# M119B.net
KiCad netlist of a schematic drawn in EAGLE
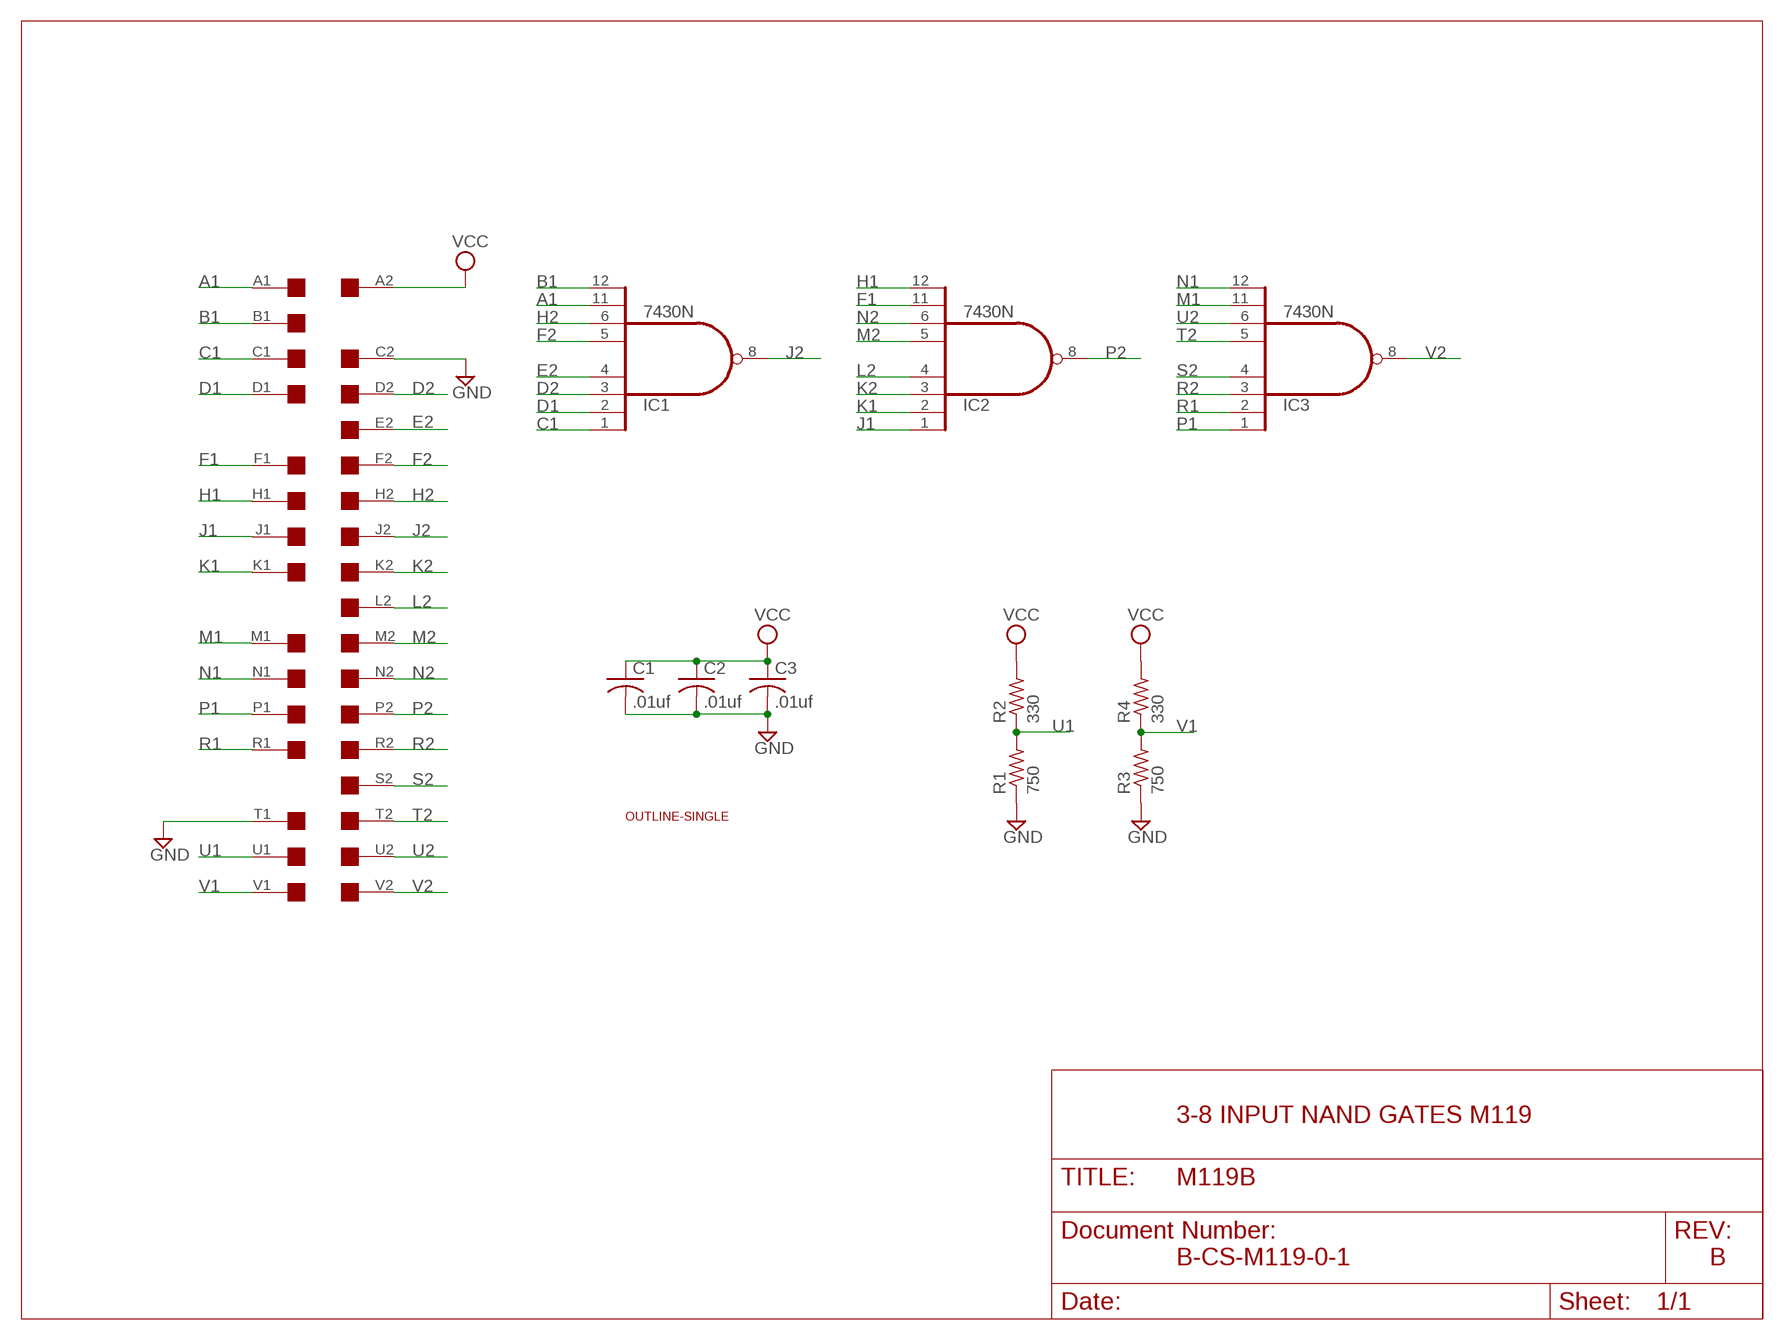
[diagram p0: schematic, sheet 1]

(export (version "E")
  (design (tool "Eeschema 10.0.6"))
  (components
    (comp (ref "C1")
      (value ".01uf")
      (footprint "eagle-import:C050-025X075")
      (libsource (lib "eagle-import") (part "C-US050-025X075"))
    )
    (comp (ref "C2")
      (value ".01uf")
      (footprint "eagle-import:C050-025X075")
      (libsource (lib "eagle-import") (part "C-US050-025X075"))
    )
    (comp (ref "C3")
      (value ".01uf")
      (footprint "eagle-import:C050-025X075")
      (libsource (lib "eagle-import") (part "C-US050-025X075"))
    )
    (comp (ref "IC1")
      (value "7430N")
      (footprint "eagle-import:DIL14")
      (libsource (lib "eagle-import") (part "7430N"))
    )
    (comp (ref "IC2")
      (value "7430N")
      (footprint "eagle-import:DIL14")
      (libsource (lib "eagle-import") (part "7430N"))
    )
    (comp (ref "IC3")
      (value "7430N")
      (footprint "eagle-import:DIL14")
      (libsource (lib "eagle-import") (part "7430N"))
    )
    (comp (ref "R1")
      (value "750")
      (footprint "eagle-import:0207_10")
      (libsource (lib "eagle-import") (part "R-US_0207/10"))
    )
    (comp (ref "R2")
      (value "330")
      (footprint "eagle-import:0207_10")
      (libsource (lib "eagle-import") (part "R-US_0207/10"))
    )
    (comp (ref "R3")
      (value "750")
      (footprint "eagle-import:0207_10")
      (libsource (lib "eagle-import") (part "R-US_0207/10"))
    )
    (comp (ref "R4")
      (value "330")
      (footprint "eagle-import:0207_10")
      (libsource (lib "eagle-import") (part "R-US_0207/10"))
    )
    (comp (ref "U$1")
      (value "OUTLINE-SINGLE")
      (footprint "eagle-import:SINGLE")
      (libsource (lib "eagle-import") (part "OUTLINE-SINGLE"))
    )
    (comp (ref "U$4")
      (value "SINGLE")
      (footprint "eagle-import:EDGE-CON2")
      (libsource (lib "eagle-import") (part "SINGLE"))
    )
  )
  (nets
    (net (code "1") (name "/A1") (class "Default")
      (node (ref "IC1") (pin "11") (pinfunction "I6_11") (pintype "input"))
      (node (ref "U$4") (pin "A1") (pinfunction "1_A1") (pintype "bidirectional"))
    )
    (net (code "2") (name "/B1") (class "Default")
      (node (ref "IC1") (pin "12") (pinfunction "I7_12") (pintype "input"))
      (node (ref "U$4") (pin "B1") (pinfunction "1_B1") (pintype "bidirectional"))
    )
    (net (code "3") (name "/C1") (class "Default")
      (node (ref "IC1") (pin "1") (pinfunction "I0_1") (pintype "input"))
      (node (ref "U$4") (pin "C1") (pinfunction "1_C1") (pintype "bidirectional"))
    )
    (net (code "4") (name "/D1") (class "Default")
      (node (ref "IC1") (pin "2") (pinfunction "I1_2") (pintype "input"))
      (node (ref "U$4") (pin "D1") (pinfunction "1_D1") (pintype "bidirectional"))
    )
    (net (code "5") (name "/D2") (class "Default")
      (node (ref "IC1") (pin "3") (pinfunction "I2_3") (pintype "input"))
      (node (ref "U$4") (pin "D2") (pinfunction "1_D2") (pintype "bidirectional"))
    )
    (net (code "6") (name "/E2") (class "Default")
      (node (ref "IC1") (pin "4") (pinfunction "I3_4") (pintype "input"))
      (node (ref "U$4") (pin "E2") (pinfunction "1_E2") (pintype "bidirectional"))
    )
    (net (code "7") (name "/F1") (class "Default")
      (node (ref "IC2") (pin "11") (pinfunction "I6_11") (pintype "input"))
      (node (ref "U$4") (pin "F1") (pinfunction "1_F1") (pintype "bidirectional"))
    )
    (net (code "8") (name "/F2") (class "Default")
      (node (ref "IC1") (pin "5") (pinfunction "I4_5") (pintype "input"))
      (node (ref "U$4") (pin "F2") (pinfunction "1_F2") (pintype "bidirectional"))
    )
    (net (code "9") (name "/H1") (class "Default")
      (node (ref "IC2") (pin "12") (pinfunction "I7_12") (pintype "input"))
      (node (ref "U$4") (pin "H1") (pinfunction "1_H1") (pintype "bidirectional"))
    )
    (net (code "10") (name "/H2") (class "Default")
      (node (ref "IC1") (pin "6") (pinfunction "I5_6") (pintype "input"))
      (node (ref "U$4") (pin "H2") (pinfunction "1_H2") (pintype "bidirectional"))
    )
    (net (code "11") (name "/J1") (class "Default")
      (node (ref "IC2") (pin "1") (pinfunction "I0_1") (pintype "input"))
      (node (ref "U$4") (pin "J1") (pinfunction "1_J1") (pintype "bidirectional"))
    )
    (net (code "12") (name "/J2") (class "Default")
      (node (ref "IC1") (pin "8") (pinfunction "O_8") (pintype "output"))
      (node (ref "U$4") (pin "J2") (pinfunction "1_J2") (pintype "bidirectional"))
    )
    (net (code "13") (name "/K1") (class "Default")
      (node (ref "IC2") (pin "2") (pinfunction "I1_2") (pintype "input"))
      (node (ref "U$4") (pin "K1") (pinfunction "1_K1") (pintype "bidirectional"))
    )
    (net (code "14") (name "/K2") (class "Default")
      (node (ref "IC2") (pin "3") (pinfunction "I2_3") (pintype "input"))
      (node (ref "U$4") (pin "K2") (pinfunction "1_K2") (pintype "bidirectional"))
    )
    (net (code "15") (name "/L2") (class "Default")
      (node (ref "IC2") (pin "4") (pinfunction "I3_4") (pintype "input"))
      (node (ref "U$4") (pin "L2") (pinfunction "1_L2") (pintype "bidirectional"))
    )
    (net (code "16") (name "/M1") (class "Default")
      (node (ref "IC3") (pin "11") (pinfunction "I6_11") (pintype "input"))
      (node (ref "U$4") (pin "M1") (pinfunction "1_M1") (pintype "bidirectional"))
    )
    (net (code "17") (name "/M2") (class "Default")
      (node (ref "IC2") (pin "5") (pinfunction "I4_5") (pintype "input"))
      (node (ref "U$4") (pin "M2") (pinfunction "1_M2") (pintype "bidirectional"))
    )
    (net (code "18") (name "/N1") (class "Default")
      (node (ref "IC3") (pin "12") (pinfunction "I7_12") (pintype "input"))
      (node (ref "U$4") (pin "N1") (pinfunction "1_N1") (pintype "bidirectional"))
    )
    (net (code "19") (name "/N2") (class "Default")
      (node (ref "IC2") (pin "6") (pinfunction "I5_6") (pintype "input"))
      (node (ref "U$4") (pin "N2") (pinfunction "1_N2") (pintype "bidirectional"))
    )
    (net (code "20") (name "/P1") (class "Default")
      (node (ref "IC3") (pin "1") (pinfunction "I0_1") (pintype "input"))
      (node (ref "U$4") (pin "P1") (pinfunction "1_P1") (pintype "bidirectional"))
    )
    (net (code "21") (name "/P2") (class "Default")
      (node (ref "IC2") (pin "8") (pinfunction "O_8") (pintype "output"))
      (node (ref "U$4") (pin "P2") (pinfunction "1_P2") (pintype "bidirectional"))
    )
    (net (code "22") (name "/R1") (class "Default")
      (node (ref "IC3") (pin "2") (pinfunction "I1_2") (pintype "input"))
      (node (ref "U$4") (pin "R1") (pinfunction "1_R1") (pintype "bidirectional"))
    )
    (net (code "23") (name "/R2") (class "Default")
      (node (ref "IC3") (pin "3") (pinfunction "I2_3") (pintype "input"))
      (node (ref "U$4") (pin "R2") (pinfunction "1_R2") (pintype "bidirectional"))
    )
    (net (code "24") (name "/S2") (class "Default")
      (node (ref "IC3") (pin "4") (pinfunction "I3_4") (pintype "input"))
      (node (ref "U$4") (pin "S2") (pinfunction "1_S2") (pintype "bidirectional"))
    )
    (net (code "25") (name "/T2") (class "Default")
      (node (ref "IC3") (pin "5") (pinfunction "I4_5") (pintype "input"))
      (node (ref "U$4") (pin "T2") (pinfunction "1_T2") (pintype "bidirectional"))
    )
    (net (code "26") (name "/U1") (class "Default")
      (node (ref "R1") (pin "2") (pinfunction "2_2") (pintype "passive"))
      (node (ref "R2") (pin "1") (pinfunction "1_1") (pintype "passive"))
      (node (ref "U$4") (pin "U1") (pinfunction "1_U1") (pintype "bidirectional"))
    )
    (net (code "27") (name "/U2") (class "Default")
      (node (ref "IC3") (pin "6") (pinfunction "I5_6") (pintype "input"))
      (node (ref "U$4") (pin "U2") (pinfunction "1_U2") (pintype "bidirectional"))
    )
    (net (code "28") (name "/V1") (class "Default")
      (node (ref "R3") (pin "2") (pinfunction "2_2") (pintype "passive"))
      (node (ref "R4") (pin "1") (pinfunction "1_1") (pintype "passive"))
      (node (ref "U$4") (pin "V1") (pinfunction "1_V1") (pintype "bidirectional"))
    )
    (net (code "29") (name "/V2") (class "Default")
      (node (ref "IC3") (pin "8") (pinfunction "O_8") (pintype "output"))
      (node (ref "U$4") (pin "V2") (pinfunction "1_V2") (pintype "bidirectional"))
    )
    (net (code "30") (name "GND") (class "Default")
      (node (ref "C1") (pin "2") (pinfunction "2_2") (pintype "passive"))
      (node (ref "C2") (pin "2") (pinfunction "2_2") (pintype "passive"))
      (node (ref "C3") (pin "2") (pinfunction "2_2") (pintype "passive"))
      (node (ref "R1") (pin "1") (pinfunction "1_1") (pintype "passive"))
      (node (ref "R3") (pin "1") (pinfunction "1_1") (pintype "passive"))
      (node (ref "U$4") (pin "C2") (pinfunction "1_C2") (pintype "bidirectional"))
      (node (ref "U$4") (pin "T1") (pinfunction "1_T1") (pintype "bidirectional"))
    )
    (net (code "31") (name "VCC") (class "Default")
      (node (ref "C1") (pin "1") (pinfunction "1_1") (pintype "passive"))
      (node (ref "C2") (pin "1") (pinfunction "1_1") (pintype "passive"))
      (node (ref "C3") (pin "1") (pinfunction "1_1") (pintype "passive"))
      (node (ref "R2") (pin "2") (pinfunction "2_2") (pintype "passive"))
      (node (ref "R4") (pin "2") (pinfunction "2_2") (pintype "passive"))
      (node (ref "U$4") (pin "A2") (pinfunction "1_A2") (pintype "bidirectional"))
    )
  )
)
